# Piano2MidiSlave.net
KiCad netlist of a schematic drawn in EAGLE
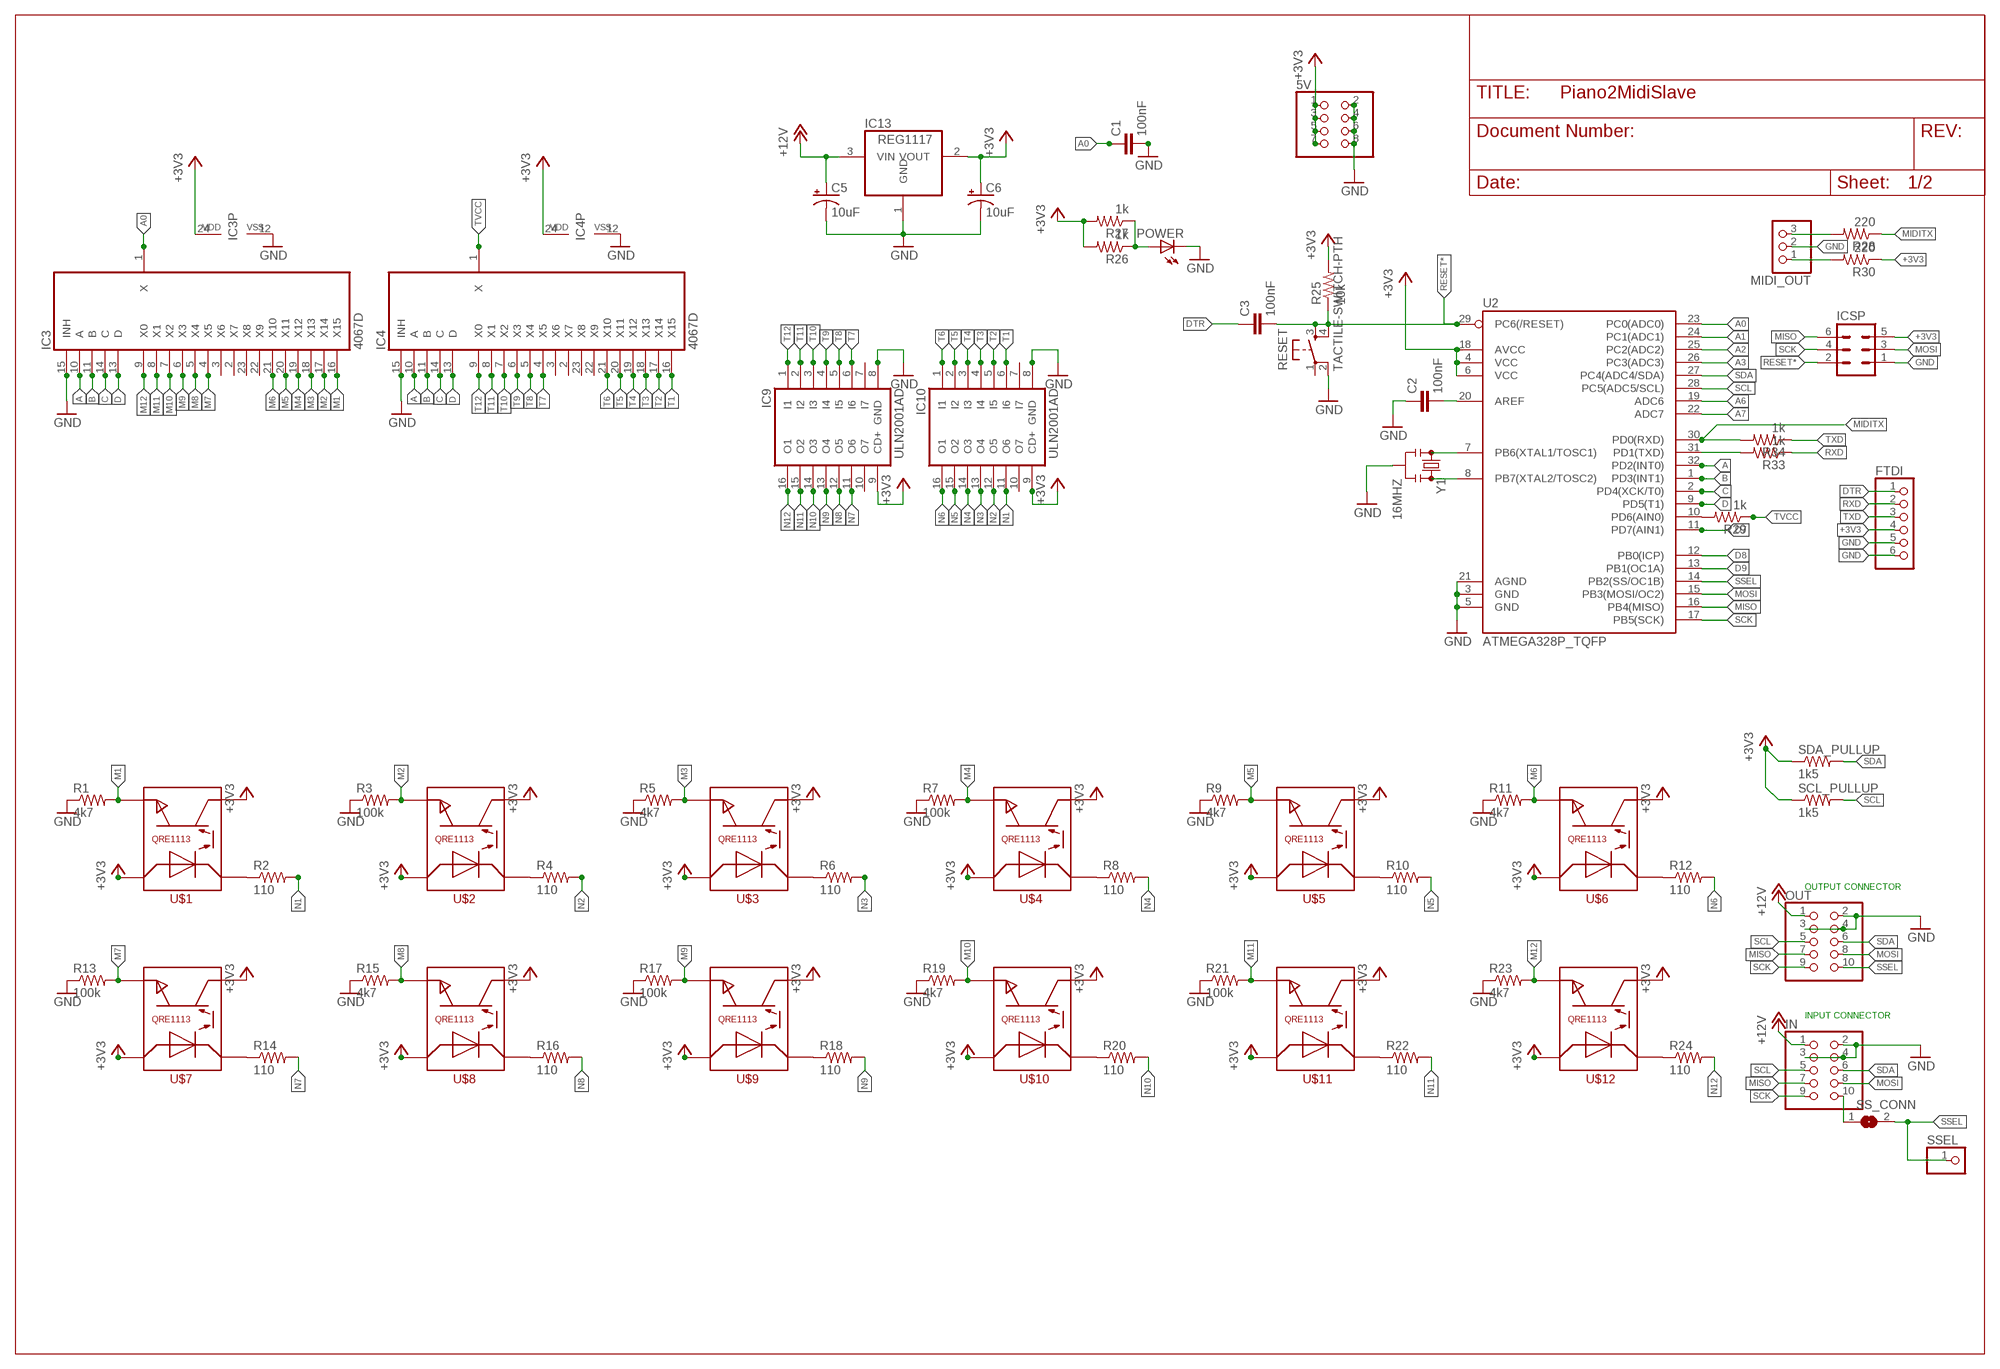
[diagram p0: schematic, sheet 1]

(export (version "E")
  (design (tool "Eeschema 10.0.6"))
  (components
    (comp (ref "5V")
      (value "PINHD-2X4")
      (footprint "eagle-import:2X04")
      (libsource (lib "eagle-import") (part "PINHD-2X4"))
    )
    (comp (ref "C1")
      (value "100nF")
      (footprint "eagle-import:C0805")
      (libsource (lib "eagle-import") (part "C"))
    )
    (comp (ref "C2")
      (value "100nF")
      (footprint "eagle-import:C0805")
      (libsource (lib "eagle-import") (part "C"))
    )
    (comp (ref "C3")
      (value "100nF")
      (footprint "eagle-import:C0805")
      (libsource (lib "eagle-import") (part "C"))
    )
    (comp (ref "C5")
      (value "10uF")
      (footprint "eagle-import:SMC_A")
      (libsource (lib "eagle-import") (part "CPOL-USSMCA"))
    )
    (comp (ref "C6")
      (value "10uF")
      (footprint "eagle-import:SMC_A")
      (libsource (lib "eagle-import") (part "CPOL-USSMCA"))
    )
    (comp (ref "FTDI")
      (value "PINHD-1X6")
      (footprint "eagle-import:1X06")
      (libsource (lib "eagle-import") (part "PINHD-1X6"))
    )
    (comp (ref "IC3")
      (value "4067D")
      (footprint "eagle-import:SO24W")
      (libsource (lib "eagle-import") (part "4067D"))
    )
    (comp (ref "IC4")
      (value "4067D")
      (footprint "eagle-import:SO24W")
      (libsource (lib "eagle-import") (part "4067D"))
    )
    (comp (ref "IC9")
      (value "ULN2001AD")
      (footprint "eagle-import:SO16")
      (libsource (lib "eagle-import") (part "ULN2001AD"))
    )
    (comp (ref "IC10")
      (value "ULN2001AD")
      (footprint "eagle-import:SO16")
      (libsource (lib "eagle-import") (part "ULN2001AD"))
    )
    (comp (ref "IC13")
      (value "REG1117")
      (footprint "eagle-import:SOT223")
      (libsource (lib "eagle-import") (part "REG1117"))
    )
    (comp (ref "ICSP")
      (value "MA03-2")
      (footprint "eagle-import:MA03-2")
      (libsource (lib "eagle-import") (part "MA03-2"))
    )
    (comp (ref "IN")
      (value "PINHD-2X5IDC")
      (footprint "eagle-import:2X05IDC")
      (libsource (lib "eagle-import") (part "PINHD-2X5IDC"))
    )
    (comp (ref "MIDI_OUT")
      (value "PINHD-1X3")
      (footprint "eagle-import:1X03")
      (libsource (lib "eagle-import") (part "PINHD-1X3"))
    )
    (comp (ref "OUT")
      (value "PINHD-2X5IDC")
      (footprint "eagle-import:2X05IDC")
      (libsource (lib "eagle-import") (part "PINHD-2X5IDC"))
    )
    (comp (ref "POWER")
      (value "LEDCHIPLED_0805")
      (footprint "eagle-import:CHIPLED_0805")
      (libsource (lib "eagle-import") (part "LEDCHIPLED_0805"))
    )
    (comp (ref "R1")
      (value "4k7")
      (footprint "eagle-import:M0805")
      (libsource (lib "eagle-import") (part "R-US_M0805"))
    )
    (comp (ref "R2")
      (value "110")
      (footprint "eagle-import:M0805")
      (libsource (lib "eagle-import") (part "R-US_M0805"))
    )
    (comp (ref "R3")
      (value "100k")
      (footprint "eagle-import:M0805")
      (libsource (lib "eagle-import") (part "R-US_M0805"))
    )
    (comp (ref "R4")
      (value "110")
      (footprint "eagle-import:M0805")
      (libsource (lib "eagle-import") (part "R-US_M0805"))
    )
    (comp (ref "R5")
      (value "4k7")
      (footprint "eagle-import:M0805")
      (libsource (lib "eagle-import") (part "R-US_M0805"))
    )
    (comp (ref "R6")
      (value "110")
      (footprint "eagle-import:M0805")
      (libsource (lib "eagle-import") (part "R-US_M0805"))
    )
    (comp (ref "R7")
      (value "100k")
      (footprint "eagle-import:M0805")
      (libsource (lib "eagle-import") (part "R-US_M0805"))
    )
    (comp (ref "R8")
      (value "110")
      (footprint "eagle-import:M0805")
      (libsource (lib "eagle-import") (part "R-US_M0805"))
    )
    (comp (ref "R9")
      (value "4k7")
      (footprint "eagle-import:M0805")
      (libsource (lib "eagle-import") (part "R-US_M0805"))
    )
    (comp (ref "R10")
      (value "110")
      (footprint "eagle-import:M0805")
      (libsource (lib "eagle-import") (part "R-US_M0805"))
    )
    (comp (ref "R11")
      (value "4k7")
      (footprint "eagle-import:M0805")
      (libsource (lib "eagle-import") (part "R-US_M0805"))
    )
    (comp (ref "R12")
      (value "110")
      (footprint "eagle-import:M0805")
      (libsource (lib "eagle-import") (part "R-US_M0805"))
    )
    (comp (ref "R13")
      (value "100k")
      (footprint "eagle-import:M0805")
      (libsource (lib "eagle-import") (part "R-US_M0805"))
    )
    (comp (ref "R14")
      (value "110")
      (footprint "eagle-import:M0805")
      (libsource (lib "eagle-import") (part "R-US_M0805"))
    )
    (comp (ref "R15")
      (value "4k7")
      (footprint "eagle-import:M0805")
      (libsource (lib "eagle-import") (part "R-US_M0805"))
    )
    (comp (ref "R16")
      (value "110")
      (footprint "eagle-import:M0805")
      (libsource (lib "eagle-import") (part "R-US_M0805"))
    )
    (comp (ref "R17")
      (value "100k")
      (footprint "eagle-import:M0805")
      (libsource (lib "eagle-import") (part "R-US_M0805"))
    )
    (comp (ref "R18")
      (value "110")
      (footprint "eagle-import:M0805")
      (libsource (lib "eagle-import") (part "R-US_M0805"))
    )
    (comp (ref "R19")
      (value "4k7")
      (footprint "eagle-import:M0805")
      (libsource (lib "eagle-import") (part "R-US_M0805"))
    )
    (comp (ref "R20")
      (value "110")
      (footprint "eagle-import:M0805")
      (libsource (lib "eagle-import") (part "R-US_M0805"))
    )
    (comp (ref "R21")
      (value "100k")
      (footprint "eagle-import:M0805")
      (libsource (lib "eagle-import") (part "R-US_M0805"))
    )
    (comp (ref "R22")
      (value "110")
      (footprint "eagle-import:M0805")
      (libsource (lib "eagle-import") (part "R-US_M0805"))
    )
    (comp (ref "R23")
      (value "4k7")
      (footprint "eagle-import:M0805")
      (libsource (lib "eagle-import") (part "R-US_M0805"))
    )
    (comp (ref "R24")
      (value "110")
      (footprint "eagle-import:M0805")
      (libsource (lib "eagle-import") (part "R-US_M0805"))
    )
    (comp (ref "R25")
      (value "10k")
      (footprint "eagle-import:M0805")
      (libsource (lib "eagle-import") (part "editedadafruit_R-US_M0805"))
    )
    (comp (ref "R26")
      (value "1k")
      (footprint "eagle-import:M0805")
      (libsource (lib "eagle-import") (part "editedadafruit_R-US_M0805"))
    )
    (comp (ref "R27")
      (value "1k")
      (footprint "eagle-import:M0805")
      (libsource (lib "eagle-import") (part "editedadafruit_R-US_M0805"))
    )
    (comp (ref "R28")
      (value "220")
      (footprint "eagle-import:M0805")
      (libsource (lib "eagle-import") (part "editedadafruit_R-US_M0805"))
    )
    (comp (ref "R29")
      (value "1k")
      (footprint "eagle-import:M0805")
      (libsource (lib "eagle-import") (part "editedadafruit_R-US_M0805"))
    )
    (comp (ref "R30")
      (value "220")
      (footprint "eagle-import:M0805")
      (libsource (lib "eagle-import") (part "editedadafruit_R-US_M0805"))
    )
    (comp (ref "R33")
      (value "1k")
      (footprint "eagle-import:M0805")
      (libsource (lib "eagle-import") (part "editedadafruit_R-US_M0805"))
    )
    (comp (ref "R34")
      (value "1k")
      (footprint "eagle-import:M0805")
      (libsource (lib "eagle-import") (part "editedadafruit_R-US_M0805"))
    )
    (comp (ref "RESET")
      (value "TACTILE-SWITCH-PTH")
      (footprint "eagle-import:TAC-SWITCH-PTH")
      (libsource (lib "eagle-import") (part "TACTILE-SWITCH-PTH"))
    )
    (comp (ref "SCL_PULLUP")
      (value "1k5")
      (footprint "eagle-import:M0805")
      (libsource (lib "eagle-import") (part "editedadafruit_R-US_M0805"))
    )
    (comp (ref "SDA_PULLUP")
      (value "1k5")
      (footprint "eagle-import:M0805")
      (libsource (lib "eagle-import") (part "editedadafruit_R-US_M0805"))
    )
    (comp (ref "SSEL")
      (value "PINHD-1X1")
      (footprint "eagle-import:1X01")
      (libsource (lib "eagle-import") (part "PINHD-1X1"))
    )
    (comp (ref "SS_CONN")
      (value "SJ")
      (footprint "eagle-import:SJ")
      (libsource (lib "eagle-import") (part "SJ"))
    )
    (comp (ref "U$1")
      (value "QRE1113QRE1113")
      (footprint "eagle-import:QRE1113")
      (libsource (lib "eagle-import") (part "QRE1113QRE1113"))
    )
    (comp (ref "U$2")
      (value "QRE1113QRE1113")
      (footprint "eagle-import:QRE1113")
      (libsource (lib "eagle-import") (part "QRE1113QRE1113"))
    )
    (comp (ref "U$3")
      (value "QRE1113QRE1113")
      (footprint "eagle-import:QRE1113")
      (libsource (lib "eagle-import") (part "QRE1113QRE1113"))
    )
    (comp (ref "U$4")
      (value "QRE1113QRE1113")
      (footprint "eagle-import:QRE1113")
      (libsource (lib "eagle-import") (part "QRE1113QRE1113"))
    )
    (comp (ref "U$5")
      (value "QRE1113QRE1113")
      (footprint "eagle-import:QRE1113")
      (libsource (lib "eagle-import") (part "QRE1113QRE1113"))
    )
    (comp (ref "U$6")
      (value "QRE1113QRE1113")
      (footprint "eagle-import:QRE1113")
      (libsource (lib "eagle-import") (part "QRE1113QRE1113"))
    )
    (comp (ref "U$7")
      (value "QRE1113QRE1113")
      (footprint "eagle-import:QRE1113")
      (libsource (lib "eagle-import") (part "QRE1113QRE1113"))
    )
    (comp (ref "U$8")
      (value "QRE1113QRE1113")
      (footprint "eagle-import:QRE1113")
      (libsource (lib "eagle-import") (part "QRE1113QRE1113"))
    )
    (comp (ref "U$9")
      (value "QRE1113QRE1113")
      (footprint "eagle-import:QRE1113")
      (libsource (lib "eagle-import") (part "QRE1113QRE1113"))
    )
    (comp (ref "U$10")
      (value "QRE1113QRE1113")
      (footprint "eagle-import:QRE1113")
      (libsource (lib "eagle-import") (part "QRE1113QRE1113"))
    )
    (comp (ref "U$11")
      (value "QRE1113QRE1113")
      (footprint "eagle-import:QRE1113")
      (libsource (lib "eagle-import") (part "QRE1113QRE1113"))
    )
    (comp (ref "U$12")
      (value "QRE1113QRE1113")
      (footprint "eagle-import:QRE1113")
      (libsource (lib "eagle-import") (part "QRE1113QRE1113"))
    )
    (comp (ref "U2")
      (value "ATMEGA328P_TQFP")
      (footprint "eagle-import:TQFP32-08")
      (libsource (lib "eagle-import") (part "ATMEGA328P_TQFP"))
    )
    (comp (ref "Y1")
      (value "16MHZ")
      (footprint "eagle-import:RESONATOR-SMD")
      (libsource (lib "eagle-import") (part "RESONATOR8MHZ"))
    )
  )
  (nets
    (net (code "1") (name "+3V3") (class "Default")
      (node (ref "5V") (pin "1") (pinfunction "1_1") (pintype "passive"))
      (node (ref "5V") (pin "3") (pinfunction "3_3") (pintype "passive"))
      (node (ref "5V") (pin "5") (pinfunction "5_5") (pintype "passive"))
      (node (ref "5V") (pin "7") (pinfunction "7_7") (pintype "passive"))
      (node (ref "C6") (pin "+") (pinfunction "+_+") (pintype "passive"))
      (node (ref "FTDI") (pin "4") (pinfunction "SDA_4") (pintype "passive"))
      (node (ref "IC10") (pin "9") (pinfunction "CD+_9") (pintype "passive"))
      (node (ref "IC13") (pin "2") (pinfunction "VOUT_2") (pintype "output"))
      (node (ref "IC3") (pin "24") (pinfunction "VDD_24") (pintype "power_in"))
      (node (ref "IC4") (pin "24") (pinfunction "VDD_24") (pintype "power_in"))
      (node (ref "IC9") (pin "9") (pinfunction "CD+_9") (pintype "passive"))
      (node (ref "ICSP") (pin "5") (pinfunction "5_5") (pintype "passive"))
      (node (ref "R25") (pin "2") (pinfunction "2_2") (pintype "passive"))
      (node (ref "R26") (pin "2") (pinfunction "2_2") (pintype "passive"))
      (node (ref "R27") (pin "2") (pinfunction "2_2") (pintype "passive"))
      (node (ref "R30") (pin "1") (pinfunction "1_1") (pintype "passive"))
      (node (ref "SCL_PULLUP") (pin "1") (pinfunction "1_1") (pintype "passive"))
      (node (ref "SDA_PULLUP") (pin "1") (pinfunction "1_1") (pintype "passive"))
      (node (ref "U$1") (pin "ANODE") (pinfunction "ANODE_ANODE") (pintype "bidirectional"))
      (node (ref "U$1") (pin "COLLECTOR") (pinfunction "COLLECTOR_COLLECTOR") (pintype "bidirectional"))
      (node (ref "U$10") (pin "ANODE") (pinfunction "ANODE_ANODE") (pintype "bidirectional"))
      (node (ref "U$10") (pin "COLLECTOR") (pinfunction "COLLECTOR_COLLECTOR") (pintype "bidirectional"))
      (node (ref "U$11") (pin "ANODE") (pinfunction "ANODE_ANODE") (pintype "bidirectional"))
      (node (ref "U$11") (pin "COLLECTOR") (pinfunction "COLLECTOR_COLLECTOR") (pintype "bidirectional"))
      (node (ref "U$12") (pin "ANODE") (pinfunction "ANODE_ANODE") (pintype "bidirectional"))
      (node (ref "U$12") (pin "COLLECTOR") (pinfunction "COLLECTOR_COLLECTOR") (pintype "bidirectional"))
      (node (ref "U$2") (pin "ANODE") (pinfunction "ANODE_ANODE") (pintype "bidirectional"))
      (node (ref "U$2") (pin "COLLECTOR") (pinfunction "COLLECTOR_COLLECTOR") (pintype "bidirectional"))
      (node (ref "U$3") (pin "ANODE") (pinfunction "ANODE_ANODE") (pintype "bidirectional"))
      (node (ref "U$3") (pin "COLLECTOR") (pinfunction "COLLECTOR_COLLECTOR") (pintype "bidirectional"))
      (node (ref "U$4") (pin "ANODE") (pinfunction "ANODE_ANODE") (pintype "bidirectional"))
      (node (ref "U$4") (pin "COLLECTOR") (pinfunction "COLLECTOR_COLLECTOR") (pintype "bidirectional"))
      (node (ref "U$5") (pin "ANODE") (pinfunction "ANODE_ANODE") (pintype "bidirectional"))
      (node (ref "U$5") (pin "COLLECTOR") (pinfunction "COLLECTOR_COLLECTOR") (pintype "bidirectional"))
      (node (ref "U$6") (pin "ANODE") (pinfunction "ANODE_ANODE") (pintype "bidirectional"))
      (node (ref "U$6") (pin "COLLECTOR") (pinfunction "COLLECTOR_COLLECTOR") (pintype "bidirectional"))
      (node (ref "U$7") (pin "ANODE") (pinfunction "ANODE_ANODE") (pintype "bidirectional"))
      (node (ref "U$7") (pin "COLLECTOR") (pinfunction "COLLECTOR_COLLECTOR") (pintype "bidirectional"))
      (node (ref "U$8") (pin "ANODE") (pinfunction "ANODE_ANODE") (pintype "bidirectional"))
      (node (ref "U$8") (pin "COLLECTOR") (pinfunction "COLLECTOR_COLLECTOR") (pintype "bidirectional"))
      (node (ref "U$9") (pin "ANODE") (pinfunction "ANODE_ANODE") (pintype "bidirectional"))
      (node (ref "U$9") (pin "COLLECTOR") (pinfunction "COLLECTOR_COLLECTOR") (pintype "bidirectional"))
      (node (ref "U2") (pin "18") (pinfunction "AVCC_18") (pintype "bidirectional"))
      (node (ref "U2") (pin "4") (pinfunction "VCC_4") (pintype "bidirectional"))
      (node (ref "U2") (pin "6") (pinfunction "VCC_6") (pintype "bidirectional"))
    )
    (net (code "2") (name "+12V") (class "Default")
      (node (ref "C5") (pin "+") (pinfunction "+_+") (pintype "passive"))
      (node (ref "IC13") (pin "3") (pinfunction "VIN_3") (pintype "input"))
      (node (ref "IN") (pin "1") (pinfunction "1_1") (pintype "passive"))
      (node (ref "OUT") (pin "1") (pinfunction "1_1") (pintype "passive"))
    )
    (net (code "3") (name "A") (class "Default")
      (node (ref "IC3") (pin "10") (pinfunction "A_10") (pintype "input"))
      (node (ref "IC4") (pin "10") (pinfunction "A_10") (pintype "input"))
      (node (ref "U2") (pin "32") (pinfunction "PD2(INT0)_32") (pintype "bidirectional"))
    )
    (net (code "4") (name "A0") (class "Default")
      (node (ref "C1") (pin "1") (pinfunction "1_1") (pintype "passive"))
      (node (ref "IC3") (pin "1") (pinfunction "X_1") (pintype "output"))
      (node (ref "U2") (pin "23") (pinfunction "PC0(ADC0)_23") (pintype "bidirectional"))
    )
    (net (code "5") (name "A1") (class "Default")
      (node (ref "U2") (pin "24") (pinfunction "PC1(ADC1)_24") (pintype "bidirectional"))
    )
    (net (code "6") (name "A2") (class "Default")
      (node (ref "U2") (pin "25") (pinfunction "PC2(ADC2)_25") (pintype "bidirectional"))
    )
    (net (code "7") (name "A3") (class "Default")
      (node (ref "U2") (pin "26") (pinfunction "PC3(ADC3)_26") (pintype "bidirectional"))
    )
    (net (code "8") (name "A6") (class "Default")
      (node (ref "U2") (pin "19") (pinfunction "ADC6_19") (pintype "bidirectional"))
    )
    (net (code "9") (name "A7") (class "Default")
      (node (ref "U2") (pin "22") (pinfunction "ADC7_22") (pintype "bidirectional"))
    )
    (net (code "10") (name "B") (class "Default")
      (node (ref "IC3") (pin "11") (pinfunction "B_11") (pintype "input"))
      (node (ref "IC4") (pin "11") (pinfunction "B_11") (pintype "input"))
      (node (ref "U2") (pin "1") (pinfunction "PD3(INT1)_1") (pintype "bidirectional"))
    )
    (net (code "11") (name "C") (class "Default")
      (node (ref "IC3") (pin "14") (pinfunction "C_14") (pintype "input"))
      (node (ref "IC4") (pin "14") (pinfunction "C_14") (pintype "input"))
      (node (ref "U2") (pin "2") (pinfunction "PD4(XCK/T0)_2") (pintype "bidirectional"))
    )
    (net (code "12") (name "D") (class "Default")
      (node (ref "IC3") (pin "13") (pinfunction "D_13") (pintype "input"))
      (node (ref "IC4") (pin "13") (pinfunction "D_13") (pintype "input"))
      (node (ref "U2") (pin "9") (pinfunction "PD5(T1)_9") (pintype "bidirectional"))
    )
    (net (code "13") (name "D7") (class "Default")
      (node (ref "U2") (pin "11") (pinfunction "PD7(AIN1)_11") (pintype "bidirectional"))
    )
    (net (code "14") (name "D8") (class "Default")
      (node (ref "U2") (pin "12") (pinfunction "PB0(ICP)_12") (pintype "bidirectional"))
    )
    (net (code "15") (name "D9") (class "Default")
      (node (ref "U2") (pin "13") (pinfunction "PB1(OC1A)_13") (pintype "bidirectional"))
    )
    (net (code "16") (name "DTR") (class "Default")
      (node (ref "C3") (pin "1") (pinfunction "1_1") (pintype "passive"))
      (node (ref "FTDI") (pin "1") (pinfunction "3V3_1") (pintype "passive"))
    )
    (net (code "17") (name "GND") (class "Default")
      (node (ref "5V") (pin "2") (pinfunction "2_2") (pintype "passive"))
      (node (ref "5V") (pin "4") (pinfunction "4_4") (pintype "passive"))
      (node (ref "5V") (pin "6") (pinfunction "6_6") (pintype "passive"))
      (node (ref "5V") (pin "8") (pinfunction "8_8") (pintype "passive"))
      (node (ref "C1") (pin "2") (pinfunction "2_2") (pintype "passive"))
      (node (ref "C2") (pin "1") (pinfunction "1_1") (pintype "passive"))
      (node (ref "C5") (pin "-") (pinfunction "-_-") (pintype "passive"))
      (node (ref "C6") (pin "-") (pinfunction "-_-") (pintype "passive"))
      (node (ref "FTDI") (pin "5") (pinfunction "ADD_5") (pintype "passive"))
      (node (ref "FTDI") (pin "6") (pinfunction "GND_6") (pintype "passive"))
      (node (ref "IC10") (pin "8") (pinfunction "GND_8") (pintype "power_in"))
      (node (ref "IC13") (pin "1") (pinfunction "GND_1") (pintype "power_in"))
      (node (ref "IC3") (pin "12") (pinfunction "VSS_12") (pintype "power_in"))
      (node (ref "IC3") (pin "15") (pinfunction "INH_15") (pintype "input"))
      (node (ref "IC4") (pin "12") (pinfunction "VSS_12") (pintype "power_in"))
      (node (ref "IC4") (pin "15") (pinfunction "INH_15") (pintype "input"))
      (node (ref "IC9") (pin "8") (pinfunction "GND_8") (pintype "power_in"))
      (node (ref "ICSP") (pin "1") (pinfunction "1_1") (pintype "passive"))
      (node (ref "IN") (pin "2") (pinfunction "2_2") (pintype "passive"))
      (node (ref "IN") (pin "3") (pinfunction "3_3") (pintype "passive"))
      (node (ref "IN") (pin "4") (pinfunction "4_4") (pintype "passive"))
      (node (ref "MIDI_OUT") (pin "2") (pinfunction "2_2") (pintype "passive"))
      (node (ref "OUT") (pin "2") (pinfunction "2_2") (pintype "passive"))
      (node (ref "OUT") (pin "3") (pinfunction "3_3") (pintype "passive"))
      (node (ref "OUT") (pin "4") (pinfunction "4_4") (pintype "passive"))
      (node (ref "POWER") (pin "C") (pinfunction "C_C") (pintype "passive"))
      (node (ref "R1") (pin "1") (pinfunction "1_1") (pintype "passive"))
      (node (ref "R11") (pin "1") (pinfunction "1_1") (pintype "passive"))
      (node (ref "R13") (pin "1") (pinfunction "1_1") (pintype "passive"))
      (node (ref "R15") (pin "1") (pinfunction "1_1") (pintype "passive"))
      (node (ref "R17") (pin "1") (pinfunction "1_1") (pintype "passive"))
      (node (ref "R19") (pin "1") (pinfunction "1_1") (pintype "passive"))
      (node (ref "R21") (pin "1") (pinfunction "1_1") (pintype "passive"))
      (node (ref "R23") (pin "1") (pinfunction "1_1") (pintype "passive"))
      (node (ref "R3") (pin "1") (pinfunction "1_1") (pintype "passive"))
      (node (ref "R5") (pin "1") (pinfunction "1_1") (pintype "passive"))
      (node (ref "R7") (pin "1") (pinfunction "1_1") (pintype "passive"))
      (node (ref "R9") (pin "1") (pinfunction "1_1") (pintype "passive"))
      (node (ref "RESET") (pin "2") (pinfunction "2_2") (pintype "passive"))
      (node (ref "U2") (pin "21") (pinfunction "AGND_21") (pintype "bidirectional"))
      (node (ref "U2") (pin "3") (pinfunction "GND_3") (pintype "bidirectional"))
      (node (ref "U2") (pin "5") (pinfunction "GND_5") (pintype "bidirectional"))
      (node (ref "Y1") (pin "2") (pinfunction "2_2") (pintype "passive"))
    )
    (net (code "18") (name "M1") (class "Default")
      (node (ref "IC3") (pin "16") (pinfunction "X15_16") (pintype "input"))
      (node (ref "R1") (pin "2") (pinfunction "2_2") (pintype "passive"))
      (node (ref "U$1") (pin "EMITTER") (pinfunction "EMITTER_EMITTER") (pintype "bidirectional"))
    )
    (net (code "19") (name "M2") (class "Default")
      (node (ref "IC3") (pin "17") (pinfunction "X14_17") (pintype "input"))
      (node (ref "R3") (pin "2") (pinfunction "2_2") (pintype "passive"))
      (node (ref "U$2") (pin "EMITTER") (pinfunction "EMITTER_EMITTER") (pintype "bidirectional"))
    )
    (net (code "20") (name "M3") (class "Default")
      (node (ref "IC3") (pin "18") (pinfunction "X13_18") (pintype "input"))
      (node (ref "R5") (pin "2") (pinfunction "2_2") (pintype "passive"))
      (node (ref "U$3") (pin "EMITTER") (pinfunction "EMITTER_EMITTER") (pintype "bidirectional"))
    )
    (net (code "21") (name "M4") (class "Default")
      (node (ref "IC3") (pin "19") (pinfunction "X12_19") (pintype "input"))
      (node (ref "R7") (pin "2") (pinfunction "2_2") (pintype "passive"))
      (node (ref "U$4") (pin "EMITTER") (pinfunction "EMITTER_EMITTER") (pintype "bidirectional"))
    )
    (net (code "22") (name "M5") (class "Default")
      (node (ref "IC3") (pin "20") (pinfunction "X11_20") (pintype "input"))
      (node (ref "R9") (pin "2") (pinfunction "2_2") (pintype "passive"))
      (node (ref "U$5") (pin "EMITTER") (pinfunction "EMITTER_EMITTER") (pintype "bidirectional"))
    )
    (net (code "23") (name "M6") (class "Default")
      (node (ref "IC3") (pin "21") (pinfunction "X10_21") (pintype "input"))
      (node (ref "R11") (pin "2") (pinfunction "2_2") (pintype "passive"))
      (node (ref "U$6") (pin "EMITTER") (pinfunction "EMITTER_EMITTER") (pintype "bidirectional"))
    )
    (net (code "24") (name "M7") (class "Default")
      (node (ref "IC3") (pin "4") (pinfunction "X5_4") (pintype "input"))
      (node (ref "R13") (pin "2") (pinfunction "2_2") (pintype "passive"))
      (node (ref "U$7") (pin "EMITTER") (pinfunction "EMITTER_EMITTER") (pintype "bidirectional"))
    )
    (net (code "25") (name "M8") (class "Default")
      (node (ref "IC3") (pin "5") (pinfunction "X4_5") (pintype "input"))
      (node (ref "R15") (pin "2") (pinfunction "2_2") (pintype "passive"))
      (node (ref "U$8") (pin "EMITTER") (pinfunction "EMITTER_EMITTER") (pintype "bidirectional"))
    )
    (net (code "26") (name "M9") (class "Default")
      (node (ref "IC3") (pin "6") (pinfunction "X3_6") (pintype "input"))
      (node (ref "R17") (pin "2") (pinfunction "2_2") (pintype "passive"))
      (node (ref "U$9") (pin "EMITTER") (pinfunction "EMITTER_EMITTER") (pintype "bidirectional"))
    )
    (net (code "27") (name "M10") (class "Default")
      (node (ref "IC3") (pin "7") (pinfunction "X2_7") (pintype "input"))
      (node (ref "R19") (pin "2") (pinfunction "2_2") (pintype "passive"))
      (node (ref "U$10") (pin "EMITTER") (pinfunction "EMITTER_EMITTER") (pintype "bidirectional"))
    )
    (net (code "28") (name "M11") (class "Default")
      (node (ref "IC3") (pin "8") (pinfunction "X1_8") (pintype "input"))
      (node (ref "R21") (pin "2") (pinfunction "2_2") (pintype "passive"))
      (node (ref "U$11") (pin "EMITTER") (pinfunction "EMITTER_EMITTER") (pintype "bidirectional"))
    )
    (net (code "29") (name "M12") (class "Default")
      (node (ref "IC3") (pin "9") (pinfunction "X0_9") (pintype "input"))
      (node (ref "R23") (pin "2") (pinfunction "2_2") (pintype "passive"))
      (node (ref "U$12") (pin "EMITTER") (pinfunction "EMITTER_EMITTER") (pintype "bidirectional"))
    )
    (net (code "30") (name "MIDITX") (class "Default")
      (node (ref "R28") (pin "1") (pinfunction "1_1") (pintype "passive"))
      (node (ref "R34") (pin "2") (pinfunction "2_2") (pintype "passive"))
      (node (ref "U2") (pin "30") (pinfunction "PD0(RXD)_30") (pintype "bidirectional"))
    )
    (net (code "31") (name "MISO") (class "Default")
      (node (ref "ICSP") (pin "6") (pinfunction "6_6") (pintype "passive"))
      (node (ref "IN") (pin "7") (pinfunction "7_7") (pintype "passive"))
      (node (ref "OUT") (pin "7") (pinfunction "7_7") (pintype "passive"))
      (node (ref "U2") (pin "16") (pinfunction "PB4(MISO)_16") (pintype "bidirectional"))
    )
    (net (code "32") (name "MOSI") (class "Default")
      (node (ref "ICSP") (pin "3") (pinfunction "3_3") (pintype "passive"))
      (node (ref "IN") (pin "8") (pinfunction "8_8") (pintype "passive"))
      (node (ref "OUT") (pin "8") (pinfunction "8_8") (pintype "passive"))
      (node (ref "U2") (pin "15") (pinfunction "PB3(MOSI/OC2)_15") (pintype "bidirectional"))
    )
    (net (code "33") (name "N1") (class "Default")
      (node (ref "IC10") (pin "11") (pinfunction "O6_11") (pintype "open_collector"))
      (node (ref "R2") (pin "2") (pinfunction "2_2") (pintype "passive"))
    )
    (net (code "34") (name "N2") (class "Default")
      (node (ref "IC10") (pin "12") (pinfunction "O5_12") (pintype "open_collector"))
      (node (ref "R4") (pin "2") (pinfunction "2_2") (pintype "passive"))
    )
    (net (code "35") (name "N3") (class "Default")
      (node (ref "IC10") (pin "13") (pinfunction "O4_13") (pintype "open_collector"))
      (node (ref "R6") (pin "2") (pinfunction "2_2") (pintype "passive"))
    )
    (net (code "36") (name "N4") (class "Default")
      (node (ref "IC10") (pin "14") (pinfunction "O3_14") (pintype "open_collector"))
      (node (ref "R8") (pin "2") (pinfunction "2_2") (pintype "passive"))
    )
    (net (code "37") (name "N5") (class "Default")
      (node (ref "IC10") (pin "15") (pinfunction "O2_15") (pintype "open_collector"))
      (node (ref "R10") (pin "2") (pinfunction "2_2") (pintype "passive"))
    )
    (net (code "38") (name "N6") (class "Default")
      (node (ref "IC10") (pin "16") (pinfunction "O1_16") (pintype "open_collector"))
      (node (ref "R12") (pin "2") (pinfunction "2_2") (pintype "passive"))
    )
    (net (code "39") (name "N7") (class "Default")
      (node (ref "IC9") (pin "11") (pinfunction "O6_11") (pintype "open_collector"))
      (node (ref "R14") (pin "2") (pinfunction "2_2") (pintype "passive"))
    )
    (net (code "40") (name "N8") (class "Default")
      (node (ref "IC9") (pin "12") (pinfunction "O5_12") (pintype "open_collector"))
      (node (ref "R16") (pin "2") (pinfunction "2_2") (pintype "passive"))
    )
    (net (code "41") (name "N9") (class "Default")
      (node (ref "IC9") (pin "13") (pinfunction "O4_13") (pintype "open_collector"))
      (node (ref "R18") (pin "2") (pinfunction "2_2") (pintype "passive"))
    )
    (net (code "42") (name "N10") (class "Default")
      (node (ref "IC9") (pin "14") (pinfunction "O3_14") (pintype "open_collector"))
      (node (ref "R20") (pin "2") (pinfunction "2_2") (pintype "passive"))
    )
    (net (code "43") (name "N11") (class "Default")
      (node (ref "IC9") (pin "15") (pinfunction "O2_15") (pintype "open_collector"))
      (node (ref "R22") (pin "2") (pinfunction "2_2") (pintype "passive"))
    )
    (net (code "44") (name "N12") (class "Default")
      (node (ref "IC9") (pin "16") (pinfunction "O1_16") (pintype "open_collector"))
      (node (ref "R24") (pin "2") (pinfunction "2_2") (pintype "passive"))
    )
    (net (code "45") (name "Net-(IN-Pad10)") (class "Default")
      (node (ref "IN") (pin "10") (pinfunction "10_10") (pintype "passive"))
      (node (ref "SS_CONN") (pin "1") (pinfunction "1_1") (pintype "passive"))
    )
    (net (code "46") (name "Net-(MIDI_OUT-Pad1)") (class "Default")
      (node (ref "MIDI_OUT") (pin "1") (pinfunction "1_1") (pintype "passive"))
      (node (ref "R30") (pin "2") (pinfunction "2_2") (pintype "passive"))
    )
    (net (code "47") (name "Net-(MIDI_OUT-Pad3)") (class "Default")
      (node (ref "MIDI_OUT") (pin "3") (pinfunction "3_3") (pintype "passive"))
      (node (ref "R28") (pin "2") (pinfunction "2_2") (pintype "passive"))
    )
    (net (code "48") (name "Net-(POWER-PadA)") (class "Default")
      (node (ref "POWER") (pin "A") (pinfunction "A_A") (pintype "passive"))
      (node (ref "R26") (pin "1") (pinfunction "1_1") (pintype "passive"))
      (node (ref "R27") (pin "1") (pinfunction "1_1") (pintype "passive"))
    )
    (net (code "49") (name "Net-(R2-Pad1)") (class "Default")
      (node (ref "R2") (pin "1") (pinfunction "1_1") (pintype "passive"))
      (node (ref "U$1") (pin "CATHODE") (pinfunction "CATHODE_CATHODE") (pintype "bidirectional"))
    )
    (net (code "50") (name "Net-(R4-Pad1)") (class "Default")
      (node (ref "R4") (pin "1") (pinfunction "1_1") (pintype "passive"))
      (node (ref "U$2") (pin "CATHODE") (pinfunction "CATHODE_CATHODE") (pintype "bidirectional"))
    )
    (net (code "51") (name "Net-(R6-Pad1)") (class "Default")
      (node (ref "R6") (pin "1") (pinfunction "1_1") (pintype "passive"))
      (node (ref "U$3") (pin "CATHODE") (pinfunction "CATHODE_CATHODE") (pintype "bidirectional"))
    )
    (net (code "52") (name "Net-(R8-Pad1)") (class "Default")
      (node (ref "R8") (pin "1") (pinfunction "1_1") (pintype "passive"))
      (node (ref "U$4") (pin "CATHODE") (pinfunction "CATHODE_CATHODE") (pintype "bidirectional"))
    )
    (net (code "53") (name "Net-(R10-Pad1)") (class "Default")
      (node (ref "R10") (pin "1") (pinfunction "1_1") (pintype "passive"))
      (node (ref "U$5") (pin "CATHODE") (pinfunction "CATHODE_CATHODE") (pintype "bidirectional"))
    )
    (net (code "54") (name "Net-(R12-Pad1)") (class "Default")
      (node (ref "R12") (pin "1") (pinfunction "1_1") (pintype "passive"))
      (node (ref "U$6") (pin "CATHODE") (pinfunction "CATHODE_CATHODE") (pintype "bidirectional"))
    )
    (net (code "55") (name "Net-(R14-Pad1)") (class "Default")
      (node (ref "R14") (pin "1") (pinfunction "1_1") (pintype "passive"))
      (node (ref "U$7") (pin "CATHODE") (pinfunction "CATHODE_CATHODE") (pintype "bidirectional"))
    )
    (net (code "56") (name "Net-(R16-Pad1)") (class "Default")
      (node (ref "R16") (pin "1") (pinfunction "1_1") (pintype "passive"))
      (node (ref "U$8") (pin "CATHODE") (pinfunction "CATHODE_CATHODE") (pintype "bidirectional"))
    )
    (net (code "57") (name "Net-(R18-Pad1)") (class "Default")
      (node (ref "R18") (pin "1") (pinfunction "1_1") (pintype "passive"))
      (node (ref "U$9") (pin "CATHODE") (pinfunction "CATHODE_CATHODE") (pintype "bidirectional"))
    )
    (net (code "58") (name "Net-(R20-Pad1)") (class "Default")
      (node (ref "R20") (pin "1") (pinfunction "1_1") (pintype "passive"))
      (node (ref "U$10") (pin "CATHODE") (pinfunction "CATHODE_CATHODE") (pintype "bidirectional"))
    )
    (net (code "59") (name "Net-(R22-Pad1)") (class "Default")
      (node (ref "R22") (pin "1") (pinfunction "1_1") (pintype "passive"))
      (node (ref "U$11") (pin "CATHODE") (pinfunction "CATHODE_CATHODE") (pintype "bidirectional"))
    )
    (net (code "60") (name "Net-(R24-Pad1)") (class "Default")
      (node (ref "R24") (pin "1") (pinfunction "1_1") (pintype "passive"))
      (node (ref "U$12") (pin "CATHODE") (pinfunction "CATHODE_CATHODE") (pintype "bidirectional"))
    )
    (net (code "61") (name "Net-(U2-AREF)") (class "Default")
      (node (ref "C2") (pin "2") (pinfunction "2_2") (pintype "passive"))
      (node (ref "U2") (pin "20") (pinfunction "AREF_20") (pintype "bidirectional"))
    )
    (net (code "62") (name "Net-(U2-PB6(XTAL1{slash}TOSC1))") (class "Default")
      (node (ref "U2") (pin "7") (pinfunction "PB6(XTAL1/TOSC1)_7") (pintype "bidirectional"))
      (node (ref "Y1") (pin "1") (pinfunction "1_1") (pintype "passive"))
    )
    (net (code "63") (name "Net-(U2-PB7(XTAL2{slash}TOSC2))") (class "Default")
      (node (ref "U2") (pin "8") (pinfunction "PB7(XTAL2/TOSC2)_8") (pintype "bidirectional"))
      (node (ref "Y1") (pin "3") (pinfunction "3_3") (pintype "passive"))
    )
    (net (code "64") (name "Net-(U2-PD1(TXD))") (class "Default")
      (node (ref "R33") (pin "2") (pinfunction "2_2") (pintype "passive"))
      (node (ref "U2") (pin "31") (pinfunction "PD1(TXD)_31") (pintype "bidirectional"))
    )
    (net (code "65") (name "Net-(U2-PD6(AIN0))") (class "Default")
      (node (ref "R29") (pin "2") (pinfunction "2_2") (pintype "passive"))
      (node (ref "U2") (pin "10") (pinfunction "PD6(AIN0)_10") (pintype "bidirectional"))
    )
    (net (code "66") (name "RESET*") (class "Default")
      (node (ref "C3") (pin "2") (pinfunction "2_2") (pintype "passive"))
      (node (ref "ICSP") (pin "2") (pinfunction "2_2") (pintype "passive"))
      (node (ref "R25") (pin "1") (pinfunction "1_1") (pintype "passive"))
      (node (ref "RESET") (pin "3") (pinfunction "3_3") (pintype "passive"))
      (node (ref "RESET") (pin "4") (pinfunction "4_4") (pintype "passive"))
      (node (ref "U2") (pin "29") (pinfunction "PC6(/RESET)_29") (pintype "bidirectional"))
    )
    (net (code "67") (name "RXD") (class "Default")
      (node (ref "FTDI") (pin "2") (pinfunction "IRQ_2") (pintype "passive"))
      (node (ref "R33") (pin "1") (pinfunction "1_1") (pintype "passive"))
    )
    (net (code "68") (name "SCK") (class "Default")
      (node (ref "ICSP") (pin "4") (pinfunction "4_4") (pintype "passive"))
      (node (ref "IN") (pin "9") (pinfunction "9_9") (pintype "passive"))
      (node (ref "OUT") (pin "9") (pinfunction "9_9") (pintype "passive"))
      (node (ref "U2") (pin "17") (pinfunction "PB5(SCK)_17") (pintype "bidirectional"))
    )
    (net (code "69") (name "SCL") (class "Default")
      (node (ref "IN") (pin "5") (pinfunction "5_5") (pintype "passive"))
      (node (ref "OUT") (pin "5") (pinfunction "5_5") (pintype "passive"))
      (node (ref "SCL_PULLUP") (pin "2") (pinfunction "2_2") (pintype "passive"))
      (node (ref "U2") (pin "28") (pinfunction "PC5(ADC5/SCL)_28") (pintype "bidirectional"))
    )
    (net (code "70") (name "SDA") (class "Default")
      (node (ref "IN") (pin "6") (pinfunction "6_6") (pintype "passive"))
      (node (ref "OUT") (pin "6") (pinfunction "6_6") (pintype "passive"))
      (node (ref "SDA_PULLUP") (pin "2") (pinfunction "2_2") (pintype "passive"))
      (node (ref "U2") (pin "27") (pinfunction "PC4(ADC4/SDA)_27") (pintype "bidirectional"))
    )
    (net (code "71") (name "SSEL") (class "Default")
      (node (ref "OUT") (pin "10") (pinfunction "10_10") (pintype "passive"))
      (node (ref "SSEL") (pin "1") (pinfunction "1_1") (pintype "passive"))
      (node (ref "SS_CONN") (pin "2") (pinfunction "2_2") (pintype "passive"))
      (node (ref "U2") (pin "14") (pinfunction "PB2(SS/OC1B)_14") (pintype "bidirectional"))
    )
    (net (code "72") (name "T1") (class "Default")
      (node (ref "IC10") (pin "6") (pinfunction "I6_6") (pintype "input"))
      (node (ref "IC4") (pin "16") (pinfunction "X15_16") (pintype "input"))
    )
    (net (code "73") (name "T2") (class "Default")
      (node (ref "IC10") (pin "5") (pinfunction "I5_5") (pintype "input"))
      (node (ref "IC4") (pin "17") (pinfunction "X14_17") (pintype "input"))
    )
    (net (code "74") (name "T3") (class "Default")
      (node (ref "IC10") (pin "4") (pinfunction "I4_4") (pintype "input"))
      (node (ref "IC4") (pin "18") (pinfunction "X13_18") (pintype "input"))
    )
    (net (code "75") (name "T4") (class "Default")
      (node (ref "IC10") (pin "3") (pinfunction "I3_3") (pintype "input"))
      (node (ref "IC4") (pin "19") (pinfunction "X12_19") (pintype "input"))
    )
    (net (code "76") (name "T5") (class "Default")
      (node (ref "IC10") (pin "2") (pinfunction "I2_2") (pintype "input"))
      (node (ref "IC4") (pin "20") (pinfunction "X11_20") (pintype "input"))
    )
    (net (code "77") (name "T6") (class "Default")
      (node (ref "IC10") (pin "1") (pinfunction "I1_1") (pintype "input"))
      (node (ref "IC4") (pin "21") (pinfunction "X10_21") (pintype "input"))
    )
    (net (code "78") (name "T7") (class "Default")
      (node (ref "IC4") (pin "4") (pinfunction "X5_4") (pintype "input"))
      (node (ref "IC9") (pin "6") (pinfunction "I6_6") (pintype "input"))
    )
    (net (code "79") (name "T8") (class "Default")
      (node (ref "IC4") (pin "5") (pinfunction "X4_5") (pintype "input"))
      (node (ref "IC9") (pin "5") (pinfunction "I5_5") (pintype "input"))
    )
    (net (code "80") (name "T9") (class "Default")
      (node (ref "IC4") (pin "6") (pinfunction "X3_6") (pintype "input"))
      (node (ref "IC9") (pin "4") (pinfunction "I4_4") (pintype "input"))
    )
    (net (code "81") (name "T10") (class "Default")
      (node (ref "IC4") (pin "7") (pinfunction "X2_7") (pintype "input"))
      (node (ref "IC9") (pin "3") (pinfunction "I3_3") (pintype "input"))
    )
    (net (code "82") (name "T11") (class "Default")
      (node (ref "IC4") (pin "8") (pinfunction "X1_8") (pintype "input"))
      (node (ref "IC9") (pin "2") (pinfunction "I2_2") (pintype "input"))
    )
    (net (code "83") (name "T12") (class "Default")
      (node (ref "IC4") (pin "9") (pinfunction "X0_9") (pintype "input"))
      (node (ref "IC9") (pin "1") (pinfunction "I1_1") (pintype "input"))
    )
    (net (code "84") (name "TVCC") (class "Default")
      (node (ref "IC4") (pin "1") (pinfunction "X_1") (pintype "output"))
      (node (ref "R29") (pin "1") (pinfunction "1_1") (pintype "passive"))
    )
    (net (code "85") (name "TXD") (class "Default")
      (node (ref "FTDI") (pin "3") (pinfunction "SCL_3") (pintype "passive"))
      (node (ref "R34") (pin "1") (pinfunction "1_1") (pintype "passive"))
    )
    (net (code "86") (name "unconnected-(IC3A-X6-Pad3)") (class "Default")
      (node (ref "IC3") (pin "3") (pinfunction "X6_3") (pintype "input"))
    )
    (net (code "87") (name "unconnected-(IC3A-X7-Pad2)") (class "Default")
      (node (ref "IC3") (pin "2") (pinfunction "X7_2") (pintype "input"))
    )
    (net (code "88") (name "unconnected-(IC3A-X8-Pad23)") (class "Default")
      (node (ref "IC3") (pin "23") (pinfunction "X8_23") (pintype "input"))
    )
    (net (code "89") (name "unconnected-(IC3A-X9-Pad22)") (class "Default")
      (node (ref "IC3") (pin "22") (pinfunction "X9_22") (pintype "input"))
    )
    (net (code "90") (name "unconnected-(IC4A-X6-Pad3)") (class "Default")
      (node (ref "IC4") (pin "3") (pinfunction "X6_3") (pintype "input"))
    )
    (net (code "91") (name "unconnected-(IC4A-X7-Pad2)") (class "Default")
      (node (ref "IC4") (pin "2") (pinfunction "X7_2") (pintype "input"))
    )
    (net (code "92") (name "unconnected-(IC4A-X8-Pad23)") (class "Default")
      (node (ref "IC4") (pin "23") (pinfunction "X8_23") (pintype "input"))
    )
    (net (code "93") (name "unconnected-(IC4A-X9-Pad22)") (class "Default")
      (node (ref "IC4") (pin "22") (pinfunction "X9_22") (pintype "input"))
    )
    (net (code "94") (name "unconnected-(IC9-I7-Pad7)") (class "Default")
      (node (ref "IC9") (pin "7") (pinfunction "I7_7") (pintype "input"))
    )
    (net (code "95") (name "unconnected-(IC9-O7-Pad10)") (class "Default")
      (node (ref "IC9") (pin "10") (pinfunction "O7_10") (pintype "open_collector"))
    )
    (net (code "96") (name "unconnected-(IC10-I7-Pad7)") (class "Default")
      (node (ref "IC10") (pin "7") (pinfunction "I7_7") (pintype "input"))
    )
    (net (code "97") (name "unconnected-(IC10-O7-Pad10)") (class "Default")
      (node (ref "IC10") (pin "10") (pinfunction "O7_10") (pintype "open_collector"))
    )
    (net (code "98") (name "unconnected-(RESET-Pad1)") (class "Default")
      (node (ref "RESET") (pin "1") (pinfunction "1_1") (pintype "passive"))
    )
  )
)
